# BANK_S_CAPACITORS.net
KiCad netlist of a schematic drawn in Altium Designer
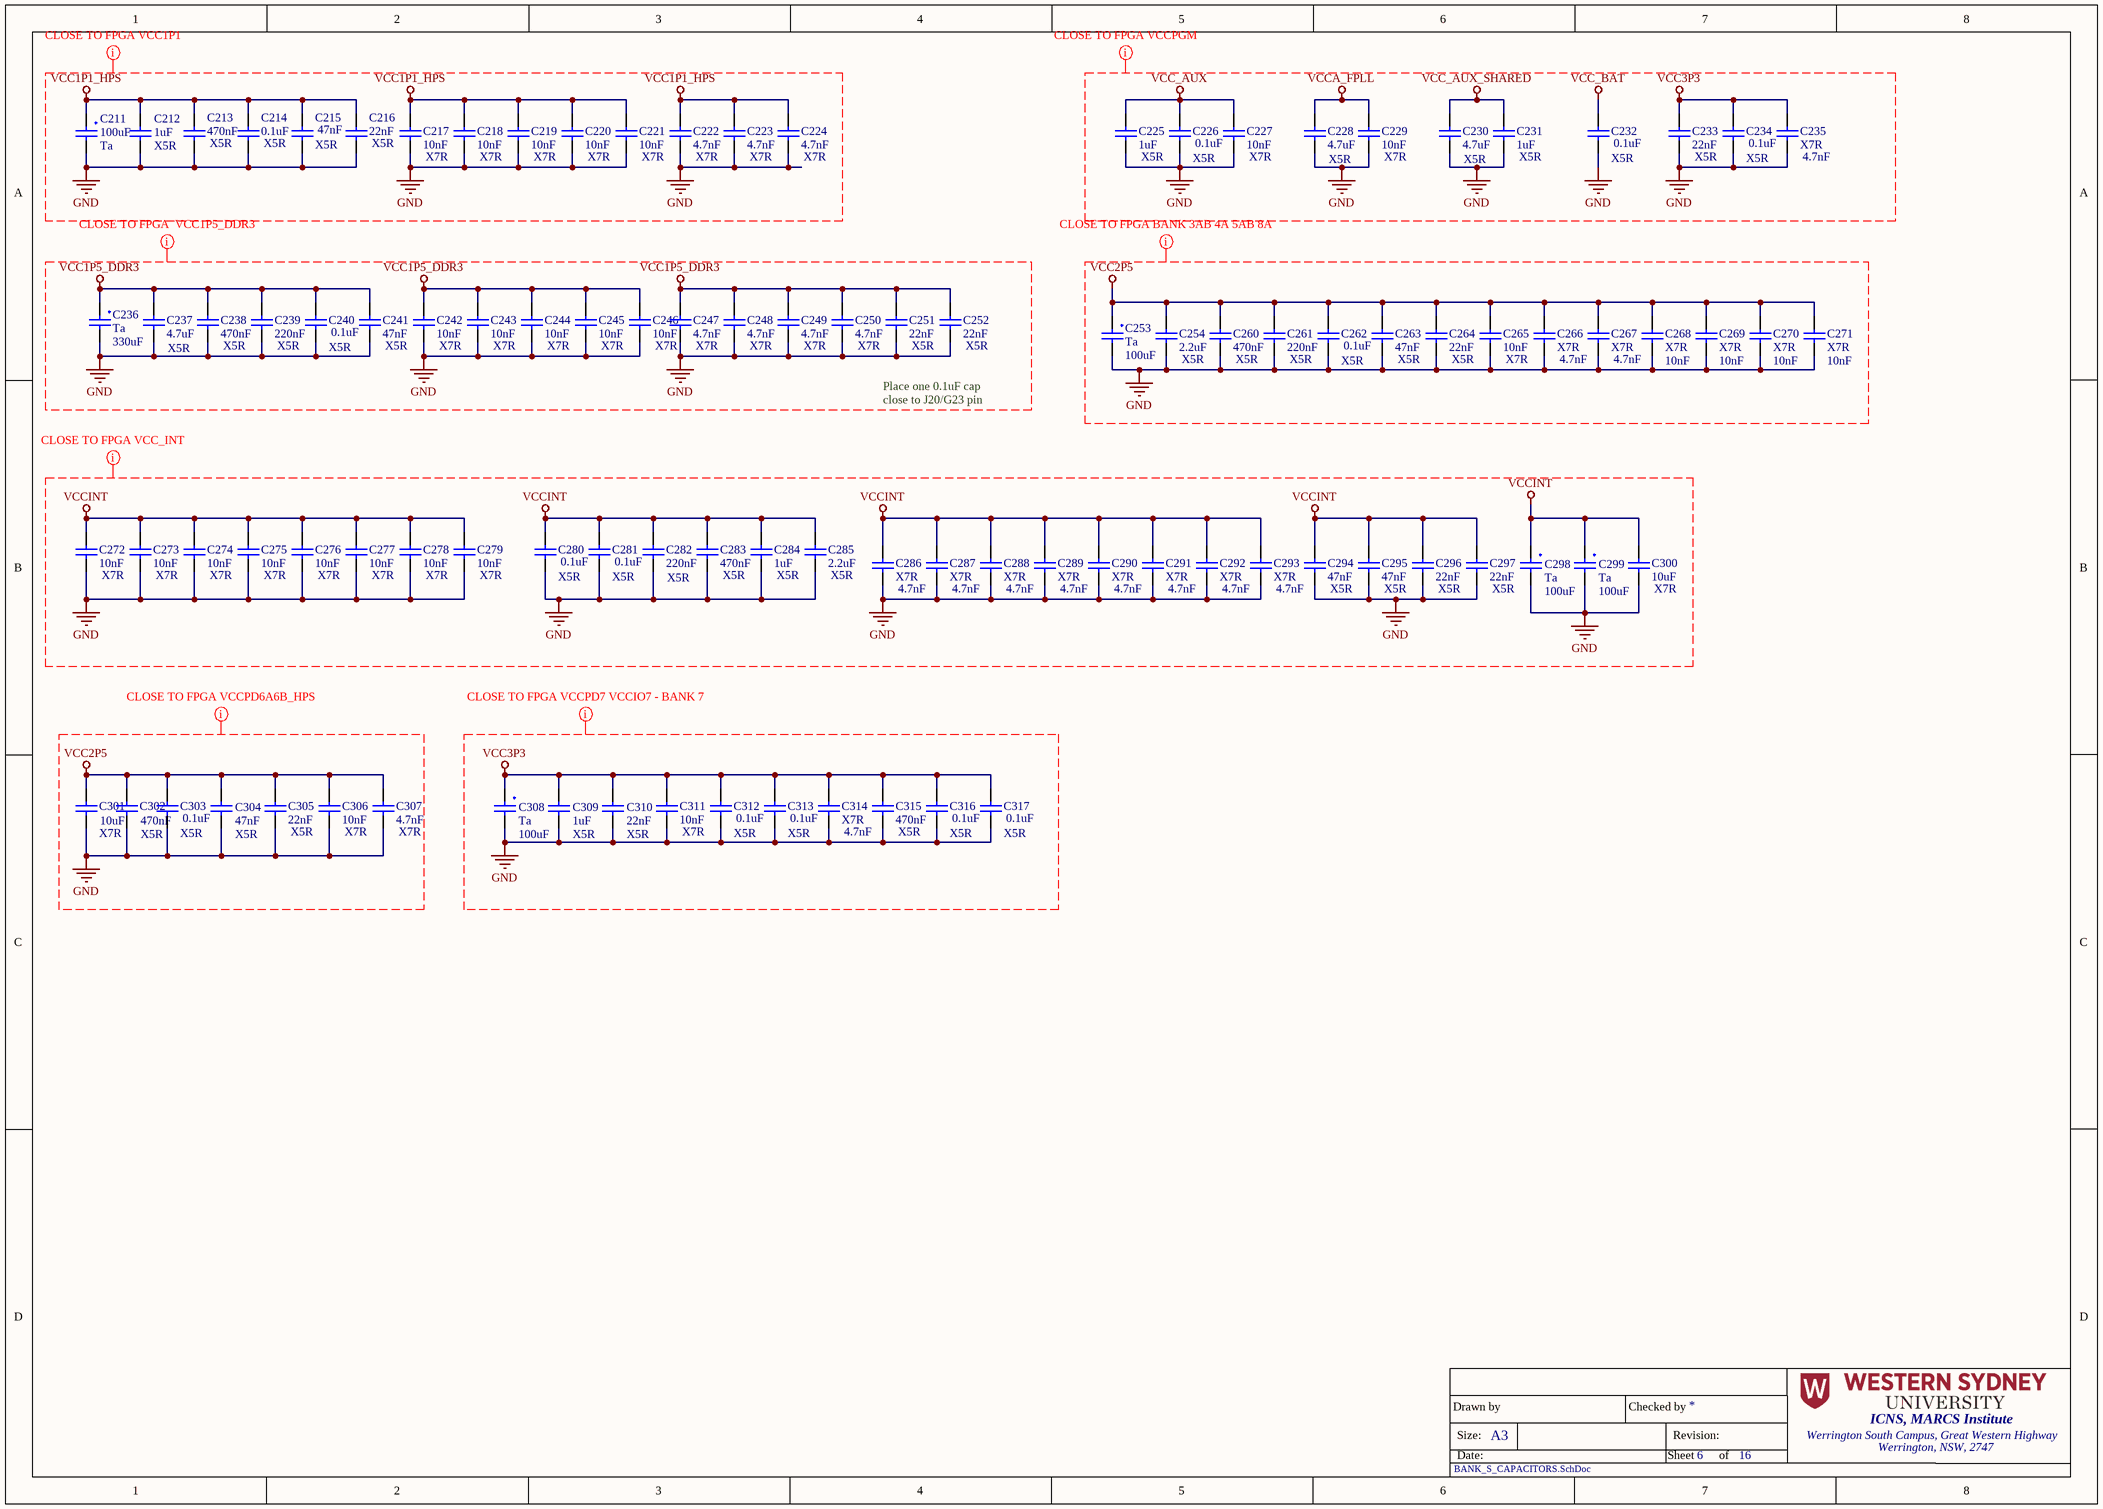
[diagram p0: BANK_S_CAPACITORS.SchDoc]

(export (version "E")
  (design (tool "Eeschema 10.0.6"))
  (components
    (comp (ref "C211")
      (value "100uF")
      (footprint "CAPCP 0805 (2012)")
      (description "Cap Tant Solid 100uF 6.3V R CASE 20% (2 X 1.35 X 1.35mm) SMD 2012-15 5 Ohm 125°C Plastic T/R")
      (fields
        (field (name "TOLERANCE") "20%")
        (field (name "DIELECTRIC") "Ta")
        (field (name "Comment") "TLCR107M006RTA")
      )
      (libsource (lib "") (part "Symbol_1"))
    )
    (comp (ref "C212")
      (value "1uF")
      (footprint "CAP 0201 (0603)")
      (description "Cap Ceramic 1uF 10V X5R 10% Pad SMD 0201 85C T/R")
      (fields
        (field (name "TOLERANCE") "10%")
        (field (name "DIELECTRIC") "X5R")
        (field (name "MANUFACTURER") "Samsung")
      )
      (libsource (lib "Western Sydney University - ICNS") (part "Symbol"))
    )
    (comp (ref "C213")
      (value "470nF")
      (footprint "CAP 0201 (0603)")
      (description "Cap Multilayer Ceramic 0.47 uF 10V X5R  0201 10% RoHS  (High dielectric type)")
      (fields
        (field (name "DIELECTRIC") "X5R")
        (field (name "MANUFACTURER") "Taiyo Yuden")
        (field (name "MANUFACTURER PART NUMBER") "LMK063BBJ474KPLF")
      )
      (libsource (lib "Western Sydney University - ICNS") (part "LMK063BBJ474KPLF"))
    )
    (comp (ref "C214")
      (value "0.1uF")
      (footprint "CAP 0201 (0603)")
      (description "Cap Ceramic 0.1uF 10V X5R 10% Pad SMD 0201 85C T/R")
      (fields
        (field (name "DIELECTRIC") "X5R")
        (field (name "MANUFACTURER") "Samsung")
        (field (name "MANUFACTURER PART NUMBER") "CL03A104KP3NNNC")
      )
      (libsource (lib "Western Sydney University - ICNS") (part "CL03A104KP3NNNC"))
    )
    (comp (ref "C215")
      (value "47nF")
      (footprint "CAP 0201 (0603)")
      (description "Cap Multilayer Ceramic 47nF 6.3V X5R SMT 0201±10% Tolerance")
      (fields
        (field (name "MANUFACTURER") "Murata")
        (field (name "TOLERANCE") "10%")
        (field (name "DIELECTRIC") "X5R")
      )
      (libsource (lib "Western Sydney University - ICNS") (part "Symbol"))
    )
    (comp (ref "C216")
      (value "22nF")
      (footprint "CAP 0201 (0603)")
      (description "Cap Multilayer Ceramic 22nF 10V X5R 0201 ±10% Tolerance")
      (fields
        (field (name "DIELECTRIC") "X5R")
        (field (name "TOLERANCE") "10%")
        (field (name "MANUFACTURER PART NUMBER") "CC0201KRX5R6BB223")
      )
      (libsource (lib "") (part "Symbol_2"))
    )
    (comp (ref "C217")
      (value "10nF")
      (footprint "CAP 0201 (0603)")
      (description "Cap Multilayer Ceramic 10nF 10V X7R 0201 ±10 % Tolerance SMT")
      (fields
        (field (name "VOLTAGE") "10V")
        (field (name "DIELECTRIC") "X7R")
        (field (name "TOLERANCE") "10%")
      )
      (libsource (lib "") (part "Symbol_2"))
    )
    (comp (ref "C218")
      (value "10nF")
      (footprint "CAP 0201 (0603)")
      (description "Cap Multilayer Ceramic 10nF 10V X7R 0201 ±10 % Tolerance SMT")
      (fields
        (field (name "VOLTAGE") "10V")
        (field (name "DIELECTRIC") "X7R")
        (field (name "TOLERANCE") "10%")
      )
      (libsource (lib "") (part "Symbol_2"))
    )
    (comp (ref "C219")
      (value "10nF")
      (footprint "CAP 0201 (0603)")
      (description "Cap Multilayer Ceramic 10nF 10V X7R 0201 ±10 % Tolerance SMT")
      (fields
        (field (name "VOLTAGE") "10V")
        (field (name "DIELECTRIC") "X7R")
        (field (name "TOLERANCE") "10%")
      )
      (libsource (lib "") (part "Symbol_2"))
    )
    (comp (ref "C220")
      (value "10nF")
      (footprint "CAP 0201 (0603)")
      (description "Cap Multilayer Ceramic 10nF 10V X7R 0201 ±10 % Tolerance SMT")
      (fields
        (field (name "VOLTAGE") "10V")
        (field (name "DIELECTRIC") "X7R")
        (field (name "TOLERANCE") "10%")
      )
      (libsource (lib "") (part "Symbol_2"))
    )
    (comp (ref "C221")
      (value "10nF")
      (footprint "CAP 0201 (0603)")
      (description "Cap Multilayer Ceramic 10nF 10V X7R 0201 ±10 % Tolerance SMT")
      (fields
        (field (name "VOLTAGE") "10V")
        (field (name "DIELECTRIC") "X7R")
        (field (name "TOLERANCE") "10%")
      )
      (libsource (lib "") (part "Symbol_2"))
    )
    (comp (ref "C222")
      (value "4.7nF")
      (footprint "CAP 0201 (0603)")
      (description "Cap Ceramic 4.7nF 6.3V X7R 10% Pad SMD 0201 125C Automotive T/R")
      (fields
        (field (name "DIELECTRIC") "X7R")
        (field (name "TOLERANCE") "10%")
        (field (name "MANUFACTURER PART NUMBER") "CC0201KRX7R5BB472")
      )
      (libsource (lib "Western Sydney University - ICNS") (part "Symbol"))
    )
    (comp (ref "C223")
      (value "4.7nF")
      (footprint "CAP 0201 (0603)")
      (description "Cap Ceramic 4.7nF 6.3V X7R 10% Pad SMD 0201 125C Automotive T/R")
      (fields
        (field (name "DIELECTRIC") "X7R")
        (field (name "TOLERANCE") "10%")
        (field (name "MANUFACTURER PART NUMBER") "CC0201KRX7R5BB472")
      )
      (libsource (lib "Western Sydney University - ICNS") (part "Symbol"))
    )
    (comp (ref "C224")
      (value "4.7nF")
      (footprint "CAP 0201 (0603)")
      (description "Cap Ceramic 4.7nF 6.3V X7R 10% Pad SMD 0201 125C Automotive T/R")
      (fields
        (field (name "DIELECTRIC") "X7R")
        (field (name "TOLERANCE") "10%")
        (field (name "MANUFACTURER PART NUMBER") "CC0201KRX7R5BB472")
      )
      (libsource (lib "Western Sydney University - ICNS") (part "Symbol"))
    )
    (comp (ref "C225")
      (value "1uF")
      (footprint "CAP 0201 (0603)")
      (description "Cap Ceramic 1uF 10V X5R 10% Pad SMD 0201 85C T/R")
      (fields
        (field (name "DIELECTRIC") "X5R")
        (field (name "TOLERANCE") "10%")
        (field (name "MANUFACTURER") "Samsung")
      )
      (libsource (lib "Western Sydney University - ICNS") (part "Symbol"))
    )
    (comp (ref "C226")
      (value "0.1uF")
      (footprint "CAP 0201 (0603)")
      (description "Cap Ceramic 0.1uF 10V X5R 10% Pad SMD 0201 85C T/R")
      (fields
        (field (name "MANUFACTURER") "Samsung")
        (field (name "TOLERANCE") "10%")
        (field (name "DIELECTRIC") "X5R")
      )
      (libsource (lib "Western Sydney University - ICNS") (part "CL03A104KP3NNNC"))
    )
    (comp (ref "C227")
      (value "10nF")
      (footprint "CAP 0201 (0603)")
      (description "Cap Multilayer Ceramic 10nF 10V X7R 0201 ±10 % Tolerance SMT")
      (fields
        (field (name "VOLTAGE") "10V")
        (field (name "DIELECTRIC") "X7R")
        (field (name "TOLERANCE") "10%")
      )
      (libsource (lib "") (part "Symbol_2"))
    )
    (comp (ref "C228")
      (value "4.7uF")
      (footprint "CAP 0402 (1005)")
      (description "Cap Multilayer Ceramic 4.7uF 10 V X5R ±10 % SMT 0402  C Series")
      (fields
        (field (name "TOLERANCE") "10%")
        (field (name "DIELECTRIC") "X5R")
        (field (name "MANUFACTURER") "TDK")
      )
      (libsource (lib "Western Sydney University - ICNS") (part "Symbol"))
    )
    (comp (ref "C229")
      (value "10nF")
      (footprint "CAP 0201 (0603)")
      (description "Cap Multilayer Ceramic 10nF 10V X7R 0201 ±10 % Tolerance SMT")
      (fields
        (field (name "VOLTAGE") "10V")
        (field (name "DIELECTRIC") "X7R")
        (field (name "TOLERANCE") "10%")
      )
      (libsource (lib "") (part "Symbol_2"))
    )
    (comp (ref "C230")
      (value "4.7uF")
      (footprint "CAP 0402 (1005)")
      (description "Cap Multilayer Ceramic 4.7uF 10 V X5R ±10 % SMT 0402  C Series")
      (fields
        (field (name "TOLERANCE") "10%")
        (field (name "DIELECTRIC") "X5R")
        (field (name "MANUFACTURER") "TDK")
      )
      (libsource (lib "Western Sydney University - ICNS") (part "Symbol"))
    )
    (comp (ref "C231")
      (value "1uF")
      (footprint "CAP 0201 (0603)")
      (description "Cap Ceramic 1uF 10V X5R 10% Pad SMD 0201 85C T/R")
      (fields
        (field (name "DIELECTRIC") "X5R")
        (field (name "TOLERANCE") "10%")
        (field (name "MANUFACTURER") "Samsung")
      )
      (libsource (lib "Western Sydney University - ICNS") (part "Symbol"))
    )
    (comp (ref "C232")
      (value "0.1uF")
      (footprint "CAP 0201 (0603)")
      (description "Cap Ceramic 0.1uF 10V X5R 10% Pad SMD 0201 85C T/R")
      (fields
        (field (name "MANUFACTURER") "Samsung")
        (field (name "TOLERANCE") "10%")
        (field (name "DIELECTRIC") "X5R")
      )
      (libsource (lib "Western Sydney University - ICNS") (part "CL03A104KP3NNNC"))
    )
    (comp (ref "C233")
      (value "22nF")
      (footprint "CAP 0201 (0603)")
      (description "Cap Multilayer Ceramic 22nF 10V X5R 0201 ±10% Tolerance")
      (fields
        (field (name "DIELECTRIC") "X5R")
        (field (name "TOLERANCE") "10%")
        (field (name "MANUFACTURER PART NUMBER") "CC0201KRX5R6BB223")
      )
      (libsource (lib "") (part "Symbol_2"))
    )
    (comp (ref "C234")
      (value "0.1uF")
      (footprint "CAP 0201 (0603)")
      (description "Cap Ceramic 0.1uF 10V X5R 10% Pad SMD 0201 85C T/R")
      (fields
        (field (name "MANUFACTURER") "Samsung")
        (field (name "TOLERANCE") "10%")
        (field (name "DIELECTRIC") "X5R")
      )
      (libsource (lib "Western Sydney University - ICNS") (part "CL03A104KP3NNNC"))
    )
    (comp (ref "C235")
      (value "CC0201KRX7R5BB472")
      (footprint "CAP 0201 (0603)")
      (description "Cap Ceramic 4.7nF 6.3V X7R 10% Pad SMD 0201 125C Automotive T/R")
      (fields
        (field (name "TOLERANCE") "10%")
        (field (name "MANUFACTURER") "Yageo")
        (field (name "CAPACITANCE") "4.7nF")
        (field (name "DIELECTRIC") "X7R")
      )
      (libsource (lib "Western Sydney University - ICNS") (part "Symbol"))
    )
    (comp (ref "C236")
      (value "330uF")
      (footprint "CAPMP7343X31N")
      (description "Cap Tant Solid 330uF 6.3V D CASE 10% (7.3 X 4.3 X 2.8mm) SMD 7343-31 0.1 Ohm 125 C T/R")
      (fields
        (field (name "VOLTAGE") "6.3V")
        (field (name "TOLERANCE") "20%")
        (field (name "DIELECTRIC") "Ta")
      )
      (libsource (lib "") (part "Symbol_1"))
    )
    (comp (ref "C237")
      (value "4.7uF")
      (footprint "CAP 0402 (1005)")
      (description "Cap Multilayer Ceramic 4.7uF 10 V X5R ±10 % SMT 0402  C Series")
      (fields
        (field (name "TOLERANCE") "10%")
        (field (name "DIELECTRIC") "X5R")
        (field (name "MANUFACTURER") "TDK")
      )
      (libsource (lib "Western Sydney University - ICNS") (part "Symbol"))
    )
    (comp (ref "C238")
      (value "470nF")
      (footprint "CAP 0201 (0603)")
      (description "Cap Multilayer Ceramic 0.47 uF 10V X5R  0201 10% RoHS  (High dielectric type)")
      (fields
        (field (name "DIELECTRIC") "X5R")
        (field (name "MANUFACTURER") "Taiyo Yuden")
        (field (name "MANUFACTURER PART NUMBER") "LMK063BBJ474KPLF")
      )
      (libsource (lib "Western Sydney University - ICNS") (part "LMK063BBJ474KPLF"))
    )
    (comp (ref "C239")
      (value "220nF")
      (footprint "CAP 0201 (0603)")
      (description "Cap Multilayer Ceramic 220nF 10V X5R 0201 ±10% Tolerance")
      (fields
        (field (name "DIELECTRIC") "X5R")
        (field (name "MANUFACTURER") "Murata")
        (field (name "MANUFACTURER PART NUMBER") "GRM033R61A224KE90D")
      )
      (libsource (lib "Western Sydney University - ICNS") (part "Symbol"))
    )
    (comp (ref "C240")
      (value "0.1uF")
      (footprint "CAP 0201 (0603)")
      (description "Cap Ceramic 0.1uF 10V X5R 10% Pad SMD 0201 85C T/R")
      (fields
        (field (name "MANUFACTURER") "Samsung")
        (field (name "TOLERANCE") "10%")
        (field (name "DIELECTRIC") "X5R")
      )
      (libsource (lib "Western Sydney University - ICNS") (part "CL03A104KP3NNNC"))
    )
    (comp (ref "C241")
      (value "47nF")
      (footprint "CAP 0201 (0603)")
      (description "Cap Multilayer Ceramic 47nF 6.3V X5R SMT 0201±10% Tolerance")
      (fields
        (field (name "DIELECTRIC") "X5R")
        (field (name "TOLERANCE") "10%")
        (field (name "MANUFACTURER PART NUMBER") "GRM033R60J473KE19D")
      )
      (libsource (lib "Western Sydney University - ICNS") (part "Symbol"))
    )
    (comp (ref "C242")
      (value "10nF")
      (footprint "CAP 0201 (0603)")
      (description "Cap Multilayer Ceramic 10nF 10V X7R 0201 ±10 % Tolerance SMT")
      (fields
        (field (name "VOLTAGE") "10V")
        (field (name "DIELECTRIC") "X7R")
        (field (name "TOLERANCE") "10%")
      )
      (libsource (lib "") (part "Symbol_2"))
    )
    (comp (ref "C243")
      (value "10nF")
      (footprint "CAP 0201 (0603)")
      (description "Cap Multilayer Ceramic 10nF 10V X7R 0201 ±10 % Tolerance SMT")
      (fields
        (field (name "VOLTAGE") "10V")
        (field (name "DIELECTRIC") "X7R")
        (field (name "TOLERANCE") "10%")
      )
      (libsource (lib "") (part "Symbol_2"))
    )
    (comp (ref "C244")
      (value "10nF")
      (footprint "CAP 0201 (0603)")
      (description "Cap Multilayer Ceramic 10nF 10V X7R 0201 ±10 % Tolerance SMT")
      (fields
        (field (name "VOLTAGE") "10V")
        (field (name "DIELECTRIC") "X7R")
        (field (name "TOLERANCE") "10%")
      )
      (libsource (lib "") (part "Symbol_2"))
    )
    (comp (ref "C245")
      (value "10nF")
      (footprint "CAP 0201 (0603)")
      (description "Cap Multilayer Ceramic 10nF 10V X7R 0201 ±10 % Tolerance SMT")
      (fields
        (field (name "VOLTAGE") "10V")
        (field (name "DIELECTRIC") "X7R")
        (field (name "TOLERANCE") "10%")
      )
      (libsource (lib "") (part "Symbol_2"))
    )
    (comp (ref "C246")
      (value "10nF")
      (footprint "CAP 0201 (0603)")
      (description "Cap Multilayer Ceramic 10nF 10V X7R 0201 ±10 % Tolerance SMT")
      (fields
        (field (name "VOLTAGE") "10V")
        (field (name "DIELECTRIC") "X7R")
        (field (name "TOLERANCE") "10%")
      )
      (libsource (lib "") (part "Symbol_2"))
    )
    (comp (ref "C247")
      (value "4.7nF")
      (footprint "CAP 0201 (0603)")
      (description "Cap Ceramic 4.7nF 6.3V X7R 10% Pad SMD 0201 125C Automotive T/R")
      (fields
        (field (name "DIELECTRIC") "X7R")
        (field (name "TOLERANCE") "10%")
        (field (name "MANUFACTURER PART NUMBER") "CC0201KRX7R5BB472")
      )
      (libsource (lib "Western Sydney University - ICNS") (part "Symbol"))
    )
    (comp (ref "C248")
      (value "4.7nF")
      (footprint "CAP 0201 (0603)")
      (description "Cap Ceramic 4.7nF 6.3V X7R 10% Pad SMD 0201 125C Automotive T/R")
      (fields
        (field (name "DIELECTRIC") "X7R")
        (field (name "TOLERANCE") "10%")
        (field (name "MANUFACTURER PART NUMBER") "CC0201KRX7R5BB472")
      )
      (libsource (lib "Western Sydney University - ICNS") (part "Symbol"))
    )
    (comp (ref "C249")
      (value "4.7nF")
      (footprint "CAP 0201 (0603)")
      (description "Cap Ceramic 4.7nF 6.3V X7R 10% Pad SMD 0201 125C Automotive T/R")
      (fields
        (field (name "DIELECTRIC") "X7R")
        (field (name "TOLERANCE") "10%")
        (field (name "MANUFACTURER PART NUMBER") "CC0201KRX7R5BB472")
      )
      (libsource (lib "Western Sydney University - ICNS") (part "Symbol"))
    )
    (comp (ref "C250")
      (value "4.7nF")
      (footprint "CAP 0201 (0603)")
      (description "Cap Ceramic 4.7nF 6.3V X7R 10% Pad SMD 0201 125C Automotive T/R")
      (fields
        (field (name "DIELECTRIC") "X7R")
        (field (name "TOLERANCE") "10%")
        (field (name "MANUFACTURER PART NUMBER") "CC0201KRX7R5BB472")
      )
      (libsource (lib "Western Sydney University - ICNS") (part "Symbol"))
    )
    (comp (ref "C251")
      (value "22nF")
      (footprint "CAP 0201 (0603)")
      (description "Cap Multilayer Ceramic 22nF 10V X5R 0201 ±10% Tolerance")
      (fields
        (field (name "DIELECTRIC") "X5R")
        (field (name "TOLERANCE") "10%")
        (field (name "MANUFACTURER PART NUMBER") "CC0201KRX5R6BB223")
      )
      (libsource (lib "") (part "Symbol_2"))
    )
    (comp (ref "C252")
      (value "22nF")
      (footprint "CAP 0201 (0603)")
      (description "Cap Multilayer Ceramic 22nF 10V X5R 0201 ±10% Tolerance")
      (fields
        (field (name "DIELECTRIC") "X5R")
        (field (name "TOLERANCE") "10%")
        (field (name "MANUFACTURER PART NUMBER") "CC0201KRX5R6BB223")
      )
      (libsource (lib "") (part "Symbol_2"))
    )
    (comp (ref "C253")
      (value "100uF")
      (footprint "CAPCP 0805 (2012)")
      (description "Cap Tant Solid 100uF 6.3V R CASE 20% (2 X 1.35 X 1.35mm) SMD 2012-15 5 Ohm 125°C Plastic T/R")
      (fields
        (field (name "TOLERANCE") "20%")
        (field (name "DIELECTRIC") "Ta")
        (field (name "Comment") "TLCR107M006RTA")
      )
      (libsource (lib "") (part "Symbol_1"))
    )
    (comp (ref "C254")
      (value "2.2uF")
      (footprint "CAP 0201 (0603)")
      (description "Cap Ceramic 2.2uF 10VDC X5R 10% SMD 0201 Paper T/R  Monolithic")
      (fields
        (field (name "DIELECTRIC") "X5R")
        (field (name "MANUFACTURER") "Murata")
        (field (name "MANUFACTURER PART NUMBER") "GRM033R61A225KE47J")
      )
      (libsource (lib "Western Sydney University - ICNS") (part "Symbol"))
    )
    (comp (ref "C260")
      (value "470nF")
      (footprint "CAP 0201 (0603)")
      (description "Cap Multilayer Ceramic 0.47 uF 10V X5R  0201 10% RoHS  (High dielectric type)")
      (fields
        (field (name "DIELECTRIC") "X5R")
        (field (name "MANUFACTURER") "Taiyo Yuden")
        (field (name "MANUFACTURER PART NUMBER") "LMK063BBJ474KPLF")
      )
      (libsource (lib "Western Sydney University - ICNS") (part "LMK063BBJ474KPLF"))
    )
    (comp (ref "C261")
      (value "220nF")
      (footprint "CAP 0201 (0603)")
      (description "Cap Multilayer Ceramic 220nF 10V X5R 0201 ±10% Tolerance")
      (fields
        (field (name "DIELECTRIC") "X5R")
        (field (name "TOLERANCE") "10%")
        (field (name "MANUFACTURER PART NUMBER") "GRM033R61A224KE90D")
      )
      (libsource (lib "Western Sydney University - ICNS") (part "Symbol"))
    )
    (comp (ref "C262")
      (value "0.1uF")
      (footprint "CAP 0201 (0603)")
      (description "Cap Ceramic 0.1uF 10V X5R 10% Pad SMD 0201 85C T/R")
      (fields
        (field (name "MANUFACTURER") "Samsung")
        (field (name "TOLERANCE") "10%")
        (field (name "DIELECTRIC") "X5R")
      )
      (libsource (lib "Western Sydney University - ICNS") (part "CL03A104KP3NNNC"))
    )
    (comp (ref "C263")
      (value "47nF")
      (footprint "CAP 0201 (0603)")
      (description "Cap Multilayer Ceramic 47nF 6.3V X5R SMT 0201±10% Tolerance")
      (fields
        (field (name "TOLERANCE") "10%")
        (field (name "DIELECTRIC") "X5R")
        (field (name "MANUFACTURER") "Murata")
      )
      (libsource (lib "Western Sydney University - ICNS") (part "Symbol"))
    )
    (comp (ref "C264")
      (value "22nF")
      (footprint "CAP 0201 (0603)")
      (description "Cap Multilayer Ceramic 22nF 10V X5R 0201 ±10% Tolerance")
      (fields
        (field (name "DIELECTRIC") "X5R")
        (field (name "TOLERANCE") "10%")
        (field (name "MANUFACTURER PART NUMBER") "CC0201KRX5R6BB223")
      )
      (libsource (lib "") (part "Symbol_2"))
    )
    (comp (ref "C265")
      (value "10nF")
      (footprint "CAP 0201 (0603)")
      (description "Cap Multilayer Ceramic 10nF 10V X7R 0201 ±10 % Tolerance SMT")
      (fields
        (field (name "VOLTAGE") "10V")
        (field (name "DIELECTRIC") "X7R")
        (field (name "TOLERANCE") "10%")
      )
      (libsource (lib "") (part "Symbol_2"))
    )
    (comp (ref "C266")
      (value "CC0201KRX7R5BB472")
      (footprint "CAP 0201 (0603)")
      (description "Cap Ceramic 4.7nF 6.3V X7R 10% Pad SMD 0201 125C Automotive T/R")
      (fields
        (field (name "TOLERANCE") "10%")
        (field (name "MANUFACTURER") "Yageo")
        (field (name "CAPACITANCE") "4.7nF")
        (field (name "DIELECTRIC") "X7R")
      )
      (libsource (lib "Western Sydney University - ICNS") (part "Symbol"))
    )
    (comp (ref "C267")
      (value "CC0201KRX7R5BB472")
      (footprint "CAP 0201 (0603)")
      (description "Cap Ceramic 4.7nF 6.3V X7R 10% Pad SMD 0201 125C Automotive T/R")
      (fields
        (field (name "TOLERANCE") "10%")
        (field (name "MANUFACTURER") "Yageo")
        (field (name "CAPACITANCE") "4.7nF")
        (field (name "DIELECTRIC") "X7R")
      )
      (libsource (lib "Western Sydney University - ICNS") (part "Symbol"))
    )
    (comp (ref "C268")
      (value "10nF")
      (footprint "CAP 0201 (0603)")
      (description "Cap Multilayer Ceramic 10nF 10V X7R 0201 ±10 % Tolerance SMT")
      (fields
        (field (name "VOLTAGE") "10V")
        (field (name "DIELECTRIC") "X7R")
        (field (name "TOLERANCE") "10%")
      )
      (libsource (lib "") (part "Symbol_2"))
    )
    (comp (ref "C269")
      (value "10nF")
      (footprint "CAP 0201 (0603)")
      (description "Cap Multilayer Ceramic 10nF 10V X7R 0201 ±10 % Tolerance SMT")
      (fields
        (field (name "VOLTAGE") "10V")
        (field (name "DIELECTRIC") "X7R")
        (field (name "TOLERANCE") "10%")
      )
      (libsource (lib "") (part "Symbol_2"))
    )
    (comp (ref "C270")
      (value "10nF")
      (footprint "CAP 0201 (0603)")
      (description "Cap Multilayer Ceramic 10nF 10V X7R 0201 ±10 % Tolerance SMT")
      (fields
        (field (name "VOLTAGE") "10V")
        (field (name "DIELECTRIC") "X7R")
        (field (name "TOLERANCE") "10%")
      )
      (libsource (lib "") (part "Symbol_2"))
    )
    (comp (ref "C271")
      (value "10nF")
      (footprint "CAP 0201 (0603)")
      (description "Cap Multilayer Ceramic 10nF 10V X7R 0201 ±10 % Tolerance SMT")
      (fields
        (field (name "VOLTAGE") "10V")
        (field (name "DIELECTRIC") "X7R")
        (field (name "TOLERANCE") "10%")
      )
      (libsource (lib "") (part "Symbol_2"))
    )
    (comp (ref "C272")
      (value "10nF")
      (footprint "CAP 0201 (0603)")
      (description "Cap Multilayer Ceramic 10nF 10V X7R 0201 ±10 % Tolerance SMT")
      (fields
        (field (name "VOLTAGE") "10V")
        (field (name "DIELECTRIC") "X7R")
        (field (name "TOLERANCE") "10%")
      )
      (libsource (lib "") (part "Symbol_2"))
    )
    (comp (ref "C273")
      (value "10nF")
      (footprint "CAP 0201 (0603)")
      (description "Cap Multilayer Ceramic 10nF 10V X7R 0201 ±10 % Tolerance SMT")
      (fields
        (field (name "VOLTAGE") "10V")
        (field (name "DIELECTRIC") "X7R")
        (field (name "TOLERANCE") "10%")
      )
      (libsource (lib "") (part "Symbol_2"))
    )
    (comp (ref "C274")
      (value "10nF")
      (footprint "CAP 0201 (0603)")
      (description "Cap Multilayer Ceramic 10nF 10V X7R 0201 ±10 % Tolerance SMT")
      (fields
        (field (name "VOLTAGE") "10V")
        (field (name "DIELECTRIC") "X7R")
        (field (name "TOLERANCE") "10%")
      )
      (libsource (lib "") (part "Symbol_2"))
    )
    (comp (ref "C275")
      (value "10nF")
      (footprint "CAP 0201 (0603)")
      (description "Cap Multilayer Ceramic 10nF 10V X7R 0201 ±10 % Tolerance SMT")
      (fields
        (field (name "VOLTAGE") "10V")
        (field (name "DIELECTRIC") "X7R")
        (field (name "TOLERANCE") "10%")
      )
      (libsource (lib "") (part "Symbol_2"))
    )
    (comp (ref "C276")
      (value "10nF")
      (footprint "CAP 0201 (0603)")
      (description "Cap Multilayer Ceramic 10nF 10V X7R 0201 ±10 % Tolerance SMT")
      (fields
        (field (name "VOLTAGE") "10V")
        (field (name "DIELECTRIC") "X7R")
        (field (name "TOLERANCE") "10%")
      )
      (libsource (lib "") (part "Symbol_2"))
    )
    (comp (ref "C277")
      (value "10nF")
      (footprint "CAP 0201 (0603)")
      (description "Cap Multilayer Ceramic 10nF 10V X7R 0201 ±10 % Tolerance SMT")
      (fields
        (field (name "VOLTAGE") "10V")
        (field (name "DIELECTRIC") "X7R")
        (field (name "TOLERANCE") "10%")
      )
      (libsource (lib "") (part "Symbol_2"))
    )
    (comp (ref "C278")
      (value "10nF")
      (footprint "CAP 0201 (0603)")
      (description "Cap Multilayer Ceramic 10nF 10V X7R 0201 ±10 % Tolerance SMT")
      (fields
        (field (name "VOLTAGE") "10V")
        (field (name "DIELECTRIC") "X7R")
        (field (name "TOLERANCE") "10%")
      )
      (libsource (lib "") (part "Symbol_2"))
    )
    (comp (ref "C279")
      (value "10nF")
      (footprint "CAP 0201 (0603)")
      (description "Cap Multilayer Ceramic 10nF 10V X7R 0201 ±10 % Tolerance SMT")
      (fields
        (field (name "VOLTAGE") "10V")
        (field (name "DIELECTRIC") "X7R")
        (field (name "TOLERANCE") "10%")
      )
      (libsource (lib "") (part "Symbol_2"))
    )
    (comp (ref "C280")
      (value "0.1uF")
      (footprint "CAP 0201 (0603)")
      (description "Cap Ceramic 0.1uF 10V X5R 10% Pad SMD 0201 85C T/R")
      (fields
        (field (name "MANUFACTURER") "Samsung")
        (field (name "TOLERANCE") "10%")
        (field (name "DIELECTRIC") "X5R")
      )
      (libsource (lib "Western Sydney University - ICNS") (part "CL03A104KP3NNNC"))
    )
    (comp (ref "C281")
      (value "0.1uF")
      (footprint "CAP 0201 (0603)")
      (description "Cap Ceramic 0.1uF 10V X5R 10% Pad SMD 0201 85C T/R")
      (fields
        (field (name "MANUFACTURER") "Samsung")
        (field (name "TOLERANCE") "10%")
        (field (name "DIELECTRIC") "X5R")
      )
      (libsource (lib "Western Sydney University - ICNS") (part "CL03A104KP3NNNC"))
    )
    (comp (ref "C282")
      (value "220nF")
      (footprint "CAP 0201 (0603)")
      (description "Cap Multilayer Ceramic 220nF 10V X5R 0201 ±10% Tolerance")
      (fields
        (field (name "DIELECTRIC") "X5R")
        (field (name "TOLERANCE") "10%")
        (field (name "MANUFACTURER PART NUMBER") "GRM033R61A224KE90D")
      )
      (libsource (lib "Western Sydney University - ICNS") (part "Symbol"))
    )
    (comp (ref "C283")
      (value "470nF")
      (footprint "CAP 0201 (0603)")
      (description "Cap Multilayer Ceramic 0.47 uF 10V X5R  0201 10% RoHS  (High dielectric type)")
      (fields
        (field (name "DIELECTRIC") "X5R")
        (field (name "MANUFACTURER") "Taiyo Yuden")
        (field (name "MANUFACTURER PART NUMBER") "LMK063BBJ474KPLF")
      )
      (libsource (lib "Western Sydney University - ICNS") (part "LMK063BBJ474KPLF"))
    )
    (comp (ref "C284")
      (value "1uF")
      (footprint "CAP 0201 (0603)")
      (description "Cap Ceramic 1uF 10V X5R 10% Pad SMD 0201 85C T/R")
      (fields
        (field (name "DIELECTRIC") "X5R")
        (field (name "TOLERANCE") "10%")
        (field (name "MANUFACTURER") "Samsung")
      )
      (libsource (lib "Western Sydney University - ICNS") (part "Symbol"))
    )
    (comp (ref "C285")
      (value "2.2uF")
      (footprint "CAP 0201 (0603)")
      (description "Cap Ceramic 2.2uF 10VDC X5R 10% SMD 0201 Paper T/R  Monolithic")
      (fields
        (field (name "DIELECTRIC") "X5R")
        (field (name "MANUFACTURER") "Murata")
        (field (name "MANUFACTURER PART NUMBER") "GRM033R61A225KE47J")
      )
      (libsource (lib "Western Sydney University - ICNS") (part "Symbol"))
    )
    (comp (ref "C286")
      (value "CC0201KRX7R5BB472")
      (footprint "CAP 0201 (0603)")
      (description "Cap Ceramic 4.7nF 6.3V X7R 10% Pad SMD 0201 125C Automotive T/R")
      (fields
        (field (name "TOLERANCE") "10%")
        (field (name "MANUFACTURER") "Yageo")
        (field (name "CAPACITANCE") "4.7nF")
        (field (name "DIELECTRIC") "X7R")
      )
      (libsource (lib "Western Sydney University - ICNS") (part "Symbol"))
    )
    (comp (ref "C287")
      (value "CC0201KRX7R5BB472")
      (footprint "CAP 0201 (0603)")
      (description "Cap Ceramic 4.7nF 6.3V X7R 10% Pad SMD 0201 125C Automotive T/R")
      (fields
        (field (name "TOLERANCE") "10%")
        (field (name "MANUFACTURER") "Yageo")
        (field (name "CAPACITANCE") "4.7nF")
        (field (name "DIELECTRIC") "X7R")
      )
      (libsource (lib "Western Sydney University - ICNS") (part "Symbol"))
    )
    (comp (ref "C288")
      (value "CC0201KRX7R5BB472")
      (footprint "CAP 0201 (0603)")
      (description "Cap Ceramic 4.7nF 6.3V X7R 10% Pad SMD 0201 125C Automotive T/R")
      (fields
        (field (name "TOLERANCE") "10%")
        (field (name "MANUFACTURER") "Yageo")
        (field (name "CAPACITANCE") "4.7nF")
        (field (name "DIELECTRIC") "X7R")
      )
      (libsource (lib "Western Sydney University - ICNS") (part "Symbol"))
    )
    (comp (ref "C289")
      (value "CC0201KRX7R5BB472")
      (footprint "CAP 0201 (0603)")
      (description "Cap Ceramic 4.7nF 6.3V X7R 10% Pad SMD 0201 125C Automotive T/R")
      (fields
        (field (name "TOLERANCE") "10%")
        (field (name "MANUFACTURER") "Yageo")
        (field (name "CAPACITANCE") "4.7nF")
        (field (name "DIELECTRIC") "X7R")
      )
      (libsource (lib "Western Sydney University - ICNS") (part "Symbol"))
    )
    (comp (ref "C290")
      (value "CC0201KRX7R5BB472")
      (footprint "CAP 0201 (0603)")
      (description "Cap Ceramic 4.7nF 6.3V X7R 10% Pad SMD 0201 125C Automotive T/R")
      (fields
        (field (name "TOLERANCE") "10%")
        (field (name "MANUFACTURER") "Yageo")
        (field (name "CAPACITANCE") "4.7nF")
        (field (name "DIELECTRIC") "X7R")
      )
      (libsource (lib "Western Sydney University - ICNS") (part "Symbol"))
    )
    (comp (ref "C291")
      (value "CC0201KRX7R5BB472")
      (footprint "CAP 0201 (0603)")
      (description "Cap Ceramic 4.7nF 6.3V X7R 10% Pad SMD 0201 125C Automotive T/R")
      (fields
        (field (name "TOLERANCE") "10%")
        (field (name "MANUFACTURER") "Yageo")
        (field (name "CAPACITANCE") "4.7nF")
        (field (name "DIELECTRIC") "X7R")
      )
      (libsource (lib "Western Sydney University - ICNS") (part "Symbol"))
    )
    (comp (ref "C292")
      (value "CC0201KRX7R5BB472")
      (footprint "CAP 0201 (0603)")
      (description "Cap Ceramic 4.7nF 6.3V X7R 10% Pad SMD 0201 125C Automotive T/R")
      (fields
        (field (name "TOLERANCE") "10%")
        (field (name "MANUFACTURER") "Yageo")
        (field (name "CAPACITANCE") "4.7nF")
        (field (name "DIELECTRIC") "X7R")
      )
      (libsource (lib "Western Sydney University - ICNS") (part "Symbol"))
    )
    (comp (ref "C293")
      (value "CC0201KRX7R5BB472")
      (footprint "CAP 0201 (0603)")
      (description "Cap Ceramic 4.7nF 6.3V X7R 10% Pad SMD 0201 125C Automotive T/R")
      (fields
        (field (name "TOLERANCE") "10%")
        (field (name "MANUFACTURER") "Yageo")
        (field (name "CAPACITANCE") "4.7nF")
        (field (name "DIELECTRIC") "X7R")
      )
      (libsource (lib "Western Sydney University - ICNS") (part "Symbol"))
    )
    (comp (ref "C294")
      (value "47nF")
      (footprint "CAP 0201 (0603)")
      (description "Cap Multilayer Ceramic 47nF 6.3V X5R SMT 0201±10% Tolerance")
      (fields
        (field (name "TOLERANCE") "10%")
        (field (name "DIELECTRIC") "X5R")
        (field (name "MANUFACTURER") "Murata")
      )
      (libsource (lib "Western Sydney University - ICNS") (part "Symbol"))
    )
    (comp (ref "C295")
      (value "47nF")
      (footprint "CAP 0201 (0603)")
      (description "Cap Multilayer Ceramic 47nF 6.3V X5R SMT 0201±10% Tolerance")
      (fields
        (field (name "TOLERANCE") "10%")
        (field (name "DIELECTRIC") "X5R")
        (field (name "MANUFACTURER") "Murata")
      )
      (libsource (lib "Western Sydney University - ICNS") (part "Symbol"))
    )
    (comp (ref "C296")
      (value "22nF")
      (footprint "CAP 0201 (0603)")
      (description "Cap Multilayer Ceramic 22nF 10V X5R 0201 ±10% Tolerance")
      (fields
        (field (name "DIELECTRIC") "X5R")
        (field (name "TOLERANCE") "10%")
        (field (name "MANUFACTURER PART NUMBER") "CC0201KRX5R6BB223")
      )
      (libsource (lib "") (part "Symbol_2"))
    )
    (comp (ref "C297")
      (value "22nF")
      (footprint "CAP 0201 (0603)")
      (description "Cap Multilayer Ceramic 22nF 10V X5R 0201 ±10% Tolerance")
      (fields
        (field (name "DIELECTRIC") "X5R")
        (field (name "TOLERANCE") "10%")
        (field (name "MANUFACTURER PART NUMBER") "CC0201KRX5R6BB223")
      )
      (libsource (lib "") (part "Symbol_2"))
    )
    (comp (ref "C298")
      (value "100uF")
      (footprint "CAPCP 0805 (2012)")
      (description "Cap Tant Solid 100uF 6.3V R CASE 20% (2 X 1.35 X 1.35mm) SMD 2012-15 5 Ohm 125°C Plastic T/R")
      (fields
        (field (name "TOLERANCE") "20%")
        (field (name "DIELECTRIC") "Ta")
        (field (name "Comment") "TLCR107M006RTA")
      )
      (libsource (lib "") (part "Symbol_1"))
    )
    (comp (ref "C299")
      (value "100uF")
      (footprint "CAPCP 0805 (2012)")
      (description "Cap Tant Solid 100uF 6.3V R CASE 20% (2 X 1.35 X 1.35mm) SMD 2012-15 5 Ohm 125°C Plastic T/R")
      (fields
        (field (name "TOLERANCE") "20%")
        (field (name "DIELECTRIC") "Ta")
        (field (name "Comment") "TLCR107M006RTA")
      )
      (libsource (lib "") (part "Symbol_1"))
    )
    (comp (ref "C300")
      (value "10uF")
      (footprint "CAP 0805 (2012)")
      (description "0805 10 uF 10 V ±10 % Tolerance X7R Surface Mount Multilayer Ceramic Capacitor")
      (fields
        (field (name "TOLERANCE") "10%")
        (field (name "DIELECTRIC") "X7R")
        (field (name "MANUFACTURER PART NUMBER") "GCM21BR71A106KE22K")
      )
      (libsource (lib "Western Sydney University - ICNS") (part "GCM21BR71A106KE22K"))
    )
    (comp (ref "C301")
      (value "GCM21BR71A106KE22K")
      (footprint "CAP 0805 (2012)")
      (description "0805 10 uF 10 V ±10 % Tolerance X7R Surface Mount Multilayer Ceramic Capacitor")
      (fields
        (field (name "DIELECTRIC") "X7R")
        (field (name "CAPACITANCE") "10uF")
        (field (name "MANUFACTURER") "Murata")
        (field (name "TOLERANCE") "10%")
      )
      (libsource (lib "Western Sydney University - ICNS") (part "GCM21BR71A106KE22K"))
    )
    (comp (ref "C302")
      (value "LMK063BBJ474KPLF")
      (footprint "CAP 0201 (0603)")
      (description "Cap Multilayer Ceramic 0.47 uF 10V X5R  0201 10% RoHS  (High dielectric type)")
      (fields
        (field (name "DIELECTRIC") "X5R")
        (field (name "CAPACITANCE") "470nF")
        (field (name "MANUFACTURER") "Taiyo Yuden")
      )
      (libsource (lib "Western Sydney University - ICNS") (part "LMK063BBJ474KPLF"))
    )
    (comp (ref "C303")
      (value "0.1uF")
      (footprint "CAP 0201 (0603)")
      (description "Cap Ceramic 0.1uF 10V X5R 10% Pad SMD 0201 85C T/R")
      (fields
        (field (name "MANUFACTURER") "Samsung")
        (field (name "TOLERANCE") "10%")
        (field (name "DIELECTRIC") "X5R")
      )
      (libsource (lib "Western Sydney University - ICNS") (part "CL03A104KP3NNNC"))
    )
    (comp (ref "C304")
      (value "47nF")
      (footprint "CAP 0201 (0603)")
      (description "Cap Multilayer Ceramic 47nF 6.3V X5R SMT 0201±10% Tolerance")
      (fields
        (field (name "TOLERANCE") "10%")
        (field (name "DIELECTRIC") "X5R")
        (field (name "MANUFACTURER") "Murata")
      )
      (libsource (lib "Western Sydney University - ICNS") (part "Symbol"))
    )
    (comp (ref "C305")
      (value "22nF")
      (footprint "CAP 0201 (0603)")
      (description "Cap Multilayer Ceramic 22nF 10V X5R 0201 ±10% Tolerance")
      (fields
        (field (name "DIELECTRIC") "X5R")
        (field (name "TOLERANCE") "10%")
        (field (name "MANUFACTURER PART NUMBER") "CC0201KRX5R6BB223")
      )
      (libsource (lib "") (part "Symbol_2"))
    )
    (comp (ref "C306")
      (value "10nF")
      (footprint "CAP 0201 (0603)")
      (description "Cap Multilayer Ceramic 10nF 10V X7R 0201 ±10 % Tolerance SMT")
      (fields
        (field (name "VOLTAGE") "10V")
        (field (name "DIELECTRIC") "X7R")
        (field (name "TOLERANCE") "10%")
      )
      (libsource (lib "") (part "Symbol_2"))
    )
    (comp (ref "C307")
      (value "4.7nF")
      (footprint "CAP 0201 (0603)")
      (description "Cap Ceramic 4.7nF 6.3V X7R 10% Pad SMD 0201 125C Automotive T/R")
      (fields
        (field (name "DIELECTRIC") "X7R")
        (field (name "TOLERANCE") "10%")
        (field (name "MANUFACTURER PART NUMBER") "CC0201KRX7R5BB472")
      )
      (libsource (lib "Western Sydney University - ICNS") (part "Symbol"))
    )
    (comp (ref "C308")
      (value "100uF")
      (footprint "CAPCP 0805 (2012)")
      (description "Cap Tant Solid 100uF 6.3V R CASE 20% (2 X 1.35 X 1.35mm) SMD 2012-15 5 Ohm 125°C Plastic T/R")
      (fields
        (field (name "TOLERANCE") "20%")
        (field (name "DIELECTRIC") "Ta")
        (field (name "Comment") "TLCR107M006RTA")
      )
      (libsource (lib "") (part "Symbol_1"))
    )
    (comp (ref "C309")
      (value "1uF")
      (footprint "CAP 0201 (0603)")
      (description "Cap Ceramic 1uF 10V X5R 10% Pad SMD 0201 85C T/R")
      (fields
        (field (name "TOLERANCE") "10%")
        (field (name "DIELECTRIC") "X5R")
        (field (name "MANUFACTURER") "Samsung")
      )
      (libsource (lib "Western Sydney University - ICNS") (part "Symbol"))
    )
    (comp (ref "C310")
      (value "22nF")
      (footprint "CAP 0201 (0603)")
      (description "Cap Multilayer Ceramic 22nF 10V X5R 0201 ±10% Tolerance")
      (fields
        (field (name "DIELECTRIC") "X5R")
        (field (name "TOLERANCE") "10%")
        (field (name "MANUFACTURER PART NUMBER") "CC0201KRX5R6BB223")
      )
      (libsource (lib "") (part "Symbol_2"))
    )
    (comp (ref "C311")
      (value "10nF")
      (footprint "CAP 0201 (0603)")
      (description "Cap Multilayer Ceramic 10nF 10V X7R 0201 ±10 % Tolerance SMT")
      (fields
        (field (name "VOLTAGE") "10V")
        (field (name "DIELECTRIC") "X7R")
        (field (name "TOLERANCE") "10%")
      )
      (libsource (lib "") (part "Symbol_2"))
    )
    (comp (ref "C312")
      (value "0.1uF")
      (footprint "CAP 0201 (0603)")
      (description "Cap Ceramic 0.1uF 10V X5R 10% Pad SMD 0201 85C T/R")
      (fields
        (field (name "MANUFACTURER") "Samsung")
        (field (name "TOLERANCE") "10%")
        (field (name "DIELECTRIC") "X5R")
      )
      (libsource (lib "Western Sydney University - ICNS") (part "CL03A104KP3NNNC"))
    )
    (comp (ref "C313")
      (value "0.1uF")
      (footprint "CAP 0201 (0603)")
      (description "Cap Ceramic 0.1uF 10V X5R 10% Pad SMD 0201 85C T/R")
      (fields
        (field (name "MANUFACTURER") "Samsung")
        (field (name "TOLERANCE") "10%")
        (field (name "DIELECTRIC") "X5R")
      )
      (libsource (lib "Western Sydney University - ICNS") (part "CL03A104KP3NNNC"))
    )
    (comp (ref "C314")
      (value "CC0201KRX7R5BB472")
      (footprint "CAP 0201 (0603)")
      (description "Cap Ceramic 4.7nF 6.3V X7R 10% Pad SMD 0201 125C Automotive T/R")
      (fields
        (field (name "TOLERANCE") "10%")
        (field (name "MANUFACTURER") "Yageo")
        (field (name "CAPACITANCE") "4.7nF")
        (field (name "DIELECTRIC") "X7R")
      )
      (libsource (lib "Western Sydney University - ICNS") (part "Symbol"))
    )
    (comp (ref "C315")
      (value "470nF")
      (footprint "CAP 0201 (0603)")
      (description "Cap Multilayer Ceramic 0.47 uF 10V X5R  0201 10% RoHS  (High dielectric type)")
      (fields
        (field (name "DIELECTRIC") "X5R")
        (field (name "MANUFACTURER") "Taiyo Yuden")
        (field (name "MANUFACTURER PART NUMBER") "LMK063BBJ474KPLF")
      )
      (libsource (lib "Western Sydney University - ICNS") (part "LMK063BBJ474KPLF"))
    )
    (comp (ref "C316")
      (value "0.1uF")
      (footprint "CAP 0201 (0603)")
      (description "Cap Ceramic 0.1uF 10V X5R 10% Pad SMD 0201 85C T/R")
      (fields
        (field (name "MANUFACTURER") "Samsung")
        (field (name "TOLERANCE") "10%")
        (field (name "DIELECTRIC") "X5R")
      )
      (libsource (lib "Western Sydney University - ICNS") (part "CL03A104KP3NNNC"))
    )
    (comp (ref "C317")
      (value "0.1uF")
      (footprint "CAP 0201 (0603)")
      (description "Cap Ceramic 0.1uF 10V X5R 10% Pad SMD 0201 85C T/R")
      (fields
        (field (name "MANUFACTURER") "Samsung")
        (field (name "TOLERANCE") "10%")
        (field (name "DIELECTRIC") "X5R")
      )
      (libsource (lib "Western Sydney University - ICNS") (part "CL03A104KP3NNNC"))
    )
  )
  (nets
    (net (code "1") (name "GND") (class "Default")
      (node (ref "C211") (pin "2") (pinfunction "2_2") (pintype "passive"))
      (node (ref "C212") (pin "2") (pinfunction "2_2") (pintype "passive"))
      (node (ref "C213") (pin "2") (pinfunction "2_2") (pintype "passive"))
      (node (ref "C214") (pin "2") (pinfunction "2_2") (pintype "passive"))
      (node (ref "C215") (pin "2") (pinfunction "2_2") (pintype "passive"))
      (node (ref "C216") (pin "2") (pinfunction "2_2") (pintype "passive"))
      (node (ref "C217") (pin "2") (pinfunction "2_2") (pintype "passive"))
      (node (ref "C218") (pin "2") (pinfunction "2_2") (pintype "passive"))
      (node (ref "C219") (pin "2") (pinfunction "2_2") (pintype "passive"))
      (node (ref "C220") (pin "2") (pinfunction "2_2") (pintype "passive"))
      (node (ref "C221") (pin "2") (pinfunction "2_2") (pintype "passive"))
      (node (ref "C222") (pin "2") (pinfunction "2_2") (pintype "passive"))
      (node (ref "C223") (pin "2") (pinfunction "2_2") (pintype "passive"))
      (node (ref "C224") (pin "2") (pinfunction "2_2") (pintype "passive"))
      (node (ref "C225") (pin "2") (pinfunction "2_2") (pintype "passive"))
      (node (ref "C226") (pin "2") (pinfunction "2_2") (pintype "passive"))
      (node (ref "C227") (pin "2") (pinfunction "2_2") (pintype "passive"))
      (node (ref "C228") (pin "2") (pinfunction "2_2") (pintype "passive"))
      (node (ref "C229") (pin "2") (pinfunction "2_2") (pintype "passive"))
      (node (ref "C230") (pin "2") (pinfunction "2_2") (pintype "passive"))
      (node (ref "C231") (pin "2") (pinfunction "2_2") (pintype "passive"))
      (node (ref "C232") (pin "2") (pinfunction "2_2") (pintype "passive"))
      (node (ref "C233") (pin "2") (pinfunction "2_2") (pintype "passive"))
      (node (ref "C234") (pin "2") (pinfunction "2_2") (pintype "passive"))
      (node (ref "C235") (pin "2") (pinfunction "2_2") (pintype "passive"))
      (node (ref "C236") (pin "2") (pinfunction "2_2") (pintype "passive"))
      (node (ref "C237") (pin "2") (pinfunction "2_2") (pintype "passive"))
      (node (ref "C238") (pin "2") (pinfunction "2_2") (pintype "passive"))
      (node (ref "C239") (pin "2") (pinfunction "2_2") (pintype "passive"))
      (node (ref "C240") (pin "2") (pinfunction "2_2") (pintype "passive"))
      (node (ref "C241") (pin "2") (pinfunction "2_2") (pintype "passive"))
      (node (ref "C242") (pin "2") (pinfunction "2_2") (pintype "passive"))
      (node (ref "C243") (pin "2") (pinfunction "2_2") (pintype "passive"))
      (node (ref "C244") (pin "2") (pinfunction "2_2") (pintype "passive"))
      (node (ref "C245") (pin "2") (pinfunction "2_2") (pintype "passive"))
      (node (ref "C246") (pin "2") (pinfunction "2_2") (pintype "passive"))
      (node (ref "C247") (pin "2") (pinfunction "2_2") (pintype "passive"))
      (node (ref "C248") (pin "2") (pinfunction "2_2") (pintype "passive"))
      (node (ref "C249") (pin "2") (pinfunction "2_2") (pintype "passive"))
      (node (ref "C250") (pin "2") (pinfunction "2_2") (pintype "passive"))
      (node (ref "C251") (pin "2") (pinfunction "2_2") (pintype "passive"))
      (node (ref "C252") (pin "2") (pinfunction "2_2") (pintype "passive"))
      (node (ref "C253") (pin "2") (pinfunction "2_2") (pintype "passive"))
      (node (ref "C254") (pin "2") (pinfunction "2_2") (pintype "passive"))
      (node (ref "C260") (pin "2") (pinfunction "2_2") (pintype "passive"))
      (node (ref "C261") (pin "2") (pinfunction "2_2") (pintype "passive"))
      (node (ref "C262") (pin "2") (pinfunction "2_2") (pintype "passive"))
      (node (ref "C263") (pin "2") (pinfunction "2_2") (pintype "passive"))
      (node (ref "C264") (pin "2") (pinfunction "2_2") (pintype "passive"))
      (node (ref "C265") (pin "2") (pinfunction "2_2") (pintype "passive"))
      (node (ref "C266") (pin "2") (pinfunction "2_2") (pintype "passive"))
      (node (ref "C267") (pin "2") (pinfunction "2_2") (pintype "passive"))
      (node (ref "C268") (pin "2") (pinfunction "2_2") (pintype "passive"))
      (node (ref "C269") (pin "2") (pinfunction "2_2") (pintype "passive"))
      (node (ref "C270") (pin "2") (pinfunction "2_2") (pintype "passive"))
      (node (ref "C271") (pin "2") (pinfunction "2_2") (pintype "passive"))
      (node (ref "C272") (pin "2") (pinfunction "2_2") (pintype "passive"))
      (node (ref "C273") (pin "2") (pinfunction "2_2") (pintype "passive"))
      (node (ref "C274") (pin "2") (pinfunction "2_2") (pintype "passive"))
      (node (ref "C275") (pin "2") (pinfunction "2_2") (pintype "passive"))
      (node (ref "C276") (pin "2") (pinfunction "2_2") (pintype "passive"))
      (node (ref "C277") (pin "2") (pinfunction "2_2") (pintype "passive"))
      (node (ref "C278") (pin "2") (pinfunction "2_2") (pintype "passive"))
      (node (ref "C279") (pin "2") (pinfunction "2_2") (pintype "passive"))
      (node (ref "C280") (pin "2") (pinfunction "2_2") (pintype "passive"))
      (node (ref "C281") (pin "2") (pinfunction "2_2") (pintype "passive"))
      (node (ref "C282") (pin "2") (pinfunction "2_2") (pintype "passive"))
      (node (ref "C283") (pin "2") (pinfunction "2_2") (pintype "passive"))
      (node (ref "C284") (pin "2") (pinfunction "2_2") (pintype "passive"))
      (node (ref "C285") (pin "2") (pinfunction "2_2") (pintype "passive"))
      (node (ref "C286") (pin "2") (pinfunction "2_2") (pintype "passive"))
      (node (ref "C287") (pin "2") (pinfunction "2_2") (pintype "passive"))
      (node (ref "C288") (pin "2") (pinfunction "2_2") (pintype "passive"))
      (node (ref "C289") (pin "2") (pinfunction "2_2") (pintype "passive"))
      (node (ref "C290") (pin "2") (pinfunction "2_2") (pintype "passive"))
      (node (ref "C291") (pin "2") (pinfunction "2_2") (pintype "passive"))
      (node (ref "C292") (pin "2") (pinfunction "2_2") (pintype "passive"))
      (node (ref "C293") (pin "2") (pinfunction "2_2") (pintype "passive"))
      (node (ref "C294") (pin "2") (pinfunction "2_2") (pintype "passive"))
      (node (ref "C295") (pin "2") (pinfunction "2_2") (pintype "passive"))
      (node (ref "C296") (pin "2") (pinfunction "2_2") (pintype "passive"))
      (node (ref "C297") (pin "2") (pinfunction "2_2") (pintype "passive"))
      (node (ref "C298") (pin "2") (pinfunction "2_2") (pintype "passive"))
      (node (ref "C299") (pin "2") (pinfunction "2_2") (pintype "passive"))
      (node (ref "C300") (pin "2") (pinfunction "2_2") (pintype "passive"))
      (node (ref "C301") (pin "2") (pinfunction "2_2") (pintype "passive"))
      (node (ref "C302") (pin "2") (pinfunction "2_2") (pintype "passive"))
      (node (ref "C303") (pin "2") (pinfunction "2_2") (pintype "passive"))
      (node (ref "C304") (pin "2") (pinfunction "2_2") (pintype "passive"))
      (node (ref "C305") (pin "2") (pinfunction "2_2") (pintype "passive"))
      (node (ref "C306") (pin "2") (pinfunction "2_2") (pintype "passive"))
      (node (ref "C307") (pin "2") (pinfunction "2_2") (pintype "passive"))
      (node (ref "C308") (pin "2") (pinfunction "2_2") (pintype "passive"))
      (node (ref "C309") (pin "2") (pinfunction "2_2") (pintype "passive"))
      (node (ref "C310") (pin "2") (pinfunction "2_2") (pintype "passive"))
      (node (ref "C311") (pin "2") (pinfunction "2_2") (pintype "passive"))
      (node (ref "C312") (pin "2") (pinfunction "2_2") (pintype "passive"))
      (node (ref "C313") (pin "2") (pinfunction "2_2") (pintype "passive"))
      (node (ref "C314") (pin "2") (pinfunction "2_2") (pintype "passive"))
      (node (ref "C315") (pin "2") (pinfunction "2_2") (pintype "passive"))
      (node (ref "C316") (pin "2") (pinfunction "2_2") (pintype "passive"))
      (node (ref "C317") (pin "2") (pinfunction "2_2") (pintype "passive"))
    )
    (net (code "2") (name "VCC1P1_HPS") (class "Default")
      (node (ref "C211") (pin "1") (pinfunction "1_1") (pintype "passive"))
      (node (ref "C212") (pin "1") (pinfunction "1_1") (pintype "passive"))
      (node (ref "C213") (pin "1") (pinfunction "1_1") (pintype "passive"))
      (node (ref "C214") (pin "1") (pinfunction "1_1") (pintype "passive"))
      (node (ref "C215") (pin "1") (pinfunction "1_1") (pintype "passive"))
      (node (ref "C216") (pin "1") (pinfunction "1_1") (pintype "passive"))
      (node (ref "C217") (pin "1") (pinfunction "1_1") (pintype "passive"))
      (node (ref "C218") (pin "1") (pinfunction "1_1") (pintype "passive"))
      (node (ref "C219") (pin "1") (pinfunction "1_1") (pintype "passive"))
      (node (ref "C220") (pin "1") (pinfunction "1_1") (pintype "passive"))
      (node (ref "C221") (pin "1") (pinfunction "1_1") (pintype "passive"))
      (node (ref "C222") (pin "1") (pinfunction "1_1") (pintype "passive"))
      (node (ref "C223") (pin "1") (pinfunction "1_1") (pintype "passive"))
      (node (ref "C224") (pin "1") (pinfunction "1_1") (pintype "passive"))
    )
    (net (code "3") (name "VCC1P5_DDR3") (class "Default")
      (node (ref "C236") (pin "1") (pinfunction "1_1") (pintype "passive"))
      (node (ref "C237") (pin "1") (pinfunction "1_1") (pintype "passive"))
      (node (ref "C238") (pin "1") (pinfunction "1_1") (pintype "passive"))
      (node (ref "C239") (pin "1") (pinfunction "1_1") (pintype "passive"))
      (node (ref "C240") (pin "1") (pinfunction "1_1") (pintype "passive"))
      (node (ref "C241") (pin "1") (pinfunction "1_1") (pintype "passive"))
      (node (ref "C242") (pin "1") (pinfunction "1_1") (pintype "passive"))
      (node (ref "C243") (pin "1") (pinfunction "1_1") (pintype "passive"))
      (node (ref "C244") (pin "1") (pinfunction "1_1") (pintype "passive"))
      (node (ref "C245") (pin "1") (pinfunction "1_1") (pintype "passive"))
      (node (ref "C246") (pin "1") (pinfunction "1_1") (pintype "passive"))
      (node (ref "C247") (pin "1") (pinfunction "1_1") (pintype "passive"))
      (node (ref "C248") (pin "1") (pinfunction "1_1") (pintype "passive"))
      (node (ref "C249") (pin "1") (pinfunction "1_1") (pintype "passive"))
      (node (ref "C250") (pin "1") (pinfunction "1_1") (pintype "passive"))
      (node (ref "C251") (pin "1") (pinfunction "1_1") (pintype "passive"))
      (node (ref "C252") (pin "1") (pinfunction "1_1") (pintype "passive"))
    )
    (net (code "4") (name "VCC2P5") (class "Default")
      (node (ref "C253") (pin "1") (pinfunction "1_1") (pintype "passive"))
      (node (ref "C254") (pin "1") (pinfunction "1_1") (pintype "passive"))
      (node (ref "C260") (pin "1") (pinfunction "1_1") (pintype "passive"))
      (node (ref "C261") (pin "1") (pinfunction "1_1") (pintype "passive"))
      (node (ref "C262") (pin "1") (pinfunction "1_1") (pintype "passive"))
      (node (ref "C263") (pin "1") (pinfunction "1_1") (pintype "passive"))
      (node (ref "C264") (pin "1") (pinfunction "1_1") (pintype "passive"))
      (node (ref "C265") (pin "1") (pinfunction "1_1") (pintype "passive"))
      (node (ref "C266") (pin "1") (pinfunction "1_1") (pintype "passive"))
      (node (ref "C267") (pin "1") (pinfunction "1_1") (pintype "passive"))
      (node (ref "C268") (pin "1") (pinfunction "1_1") (pintype "passive"))
      (node (ref "C269") (pin "1") (pinfunction "1_1") (pintype "passive"))
      (node (ref "C270") (pin "1") (pinfunction "1_1") (pintype "passive"))
      (node (ref "C271") (pin "1") (pinfunction "1_1") (pintype "passive"))
      (node (ref "C301") (pin "1") (pinfunction "1_1") (pintype "passive"))
      (node (ref "C302") (pin "1") (pinfunction "1_1") (pintype "passive"))
      (node (ref "C303") (pin "1") (pinfunction "1_1") (pintype "passive"))
      (node (ref "C304") (pin "1") (pinfunction "1_1") (pintype "passive"))
      (node (ref "C305") (pin "1") (pinfunction "1_1") (pintype "passive"))
      (node (ref "C306") (pin "1") (pinfunction "1_1") (pintype "passive"))
      (node (ref "C307") (pin "1") (pinfunction "1_1") (pintype "passive"))
    )
    (net (code "5") (name "VCC3P3") (class "Default")
      (node (ref "C233") (pin "1") (pinfunction "1_1") (pintype "passive"))
      (node (ref "C234") (pin "1") (pinfunction "1_1") (pintype "passive"))
      (node (ref "C235") (pin "1") (pinfunction "1_1") (pintype "passive"))
      (node (ref "C308") (pin "1") (pinfunction "1_1") (pintype "passive"))
      (node (ref "C309") (pin "1") (pinfunction "1_1") (pintype "passive"))
      (node (ref "C310") (pin "1") (pinfunction "1_1") (pintype "passive"))
      (node (ref "C311") (pin "1") (pinfunction "1_1") (pintype "passive"))
      (node (ref "C312") (pin "1") (pinfunction "1_1") (pintype "passive"))
      (node (ref "C313") (pin "1") (pinfunction "1_1") (pintype "passive"))
      (node (ref "C314") (pin "1") (pinfunction "1_1") (pintype "passive"))
      (node (ref "C315") (pin "1") (pinfunction "1_1") (pintype "passive"))
      (node (ref "C316") (pin "1") (pinfunction "1_1") (pintype "passive"))
      (node (ref "C317") (pin "1") (pinfunction "1_1") (pintype "passive"))
    )
    (net (code "6") (name "VCCA_FPLL") (class "Default")
      (node (ref "C228") (pin "1") (pinfunction "1_1") (pintype "passive"))
      (node (ref "C229") (pin "1") (pinfunction "1_1") (pintype "passive"))
    )
    (net (code "7") (name "VCCINT") (class "Default")
      (node (ref "C272") (pin "1") (pinfunction "1_1") (pintype "passive"))
      (node (ref "C273") (pin "1") (pinfunction "1_1") (pintype "passive"))
      (node (ref "C274") (pin "1") (pinfunction "1_1") (pintype "passive"))
      (node (ref "C275") (pin "1") (pinfunction "1_1") (pintype "passive"))
      (node (ref "C276") (pin "1") (pinfunction "1_1") (pintype "passive"))
      (node (ref "C277") (pin "1") (pinfunction "1_1") (pintype "passive"))
      (node (ref "C278") (pin "1") (pinfunction "1_1") (pintype "passive"))
      (node (ref "C279") (pin "1") (pinfunction "1_1") (pintype "passive"))
      (node (ref "C280") (pin "1") (pinfunction "1_1") (pintype "passive"))
      (node (ref "C281") (pin "1") (pinfunction "1_1") (pintype "passive"))
      (node (ref "C282") (pin "1") (pinfunction "1_1") (pintype "passive"))
      (node (ref "C283") (pin "1") (pinfunction "1_1") (pintype "passive"))
      (node (ref "C284") (pin "1") (pinfunction "1_1") (pintype "passive"))
      (node (ref "C285") (pin "1") (pinfunction "1_1") (pintype "passive"))
      (node (ref "C286") (pin "1") (pinfunction "1_1") (pintype "passive"))
      (node (ref "C287") (pin "1") (pinfunction "1_1") (pintype "passive"))
      (node (ref "C288") (pin "1") (pinfunction "1_1") (pintype "passive"))
      (node (ref "C289") (pin "1") (pinfunction "1_1") (pintype "passive"))
      (node (ref "C290") (pin "1") (pinfunction "1_1") (pintype "passive"))
      (node (ref "C291") (pin "1") (pinfunction "1_1") (pintype "passive"))
      (node (ref "C292") (pin "1") (pinfunction "1_1") (pintype "passive"))
      (node (ref "C293") (pin "1") (pinfunction "1_1") (pintype "passive"))
      (node (ref "C294") (pin "1") (pinfunction "1_1") (pintype "passive"))
      (node (ref "C295") (pin "1") (pinfunction "1_1") (pintype "passive"))
      (node (ref "C296") (pin "1") (pinfunction "1_1") (pintype "passive"))
      (node (ref "C297") (pin "1") (pinfunction "1_1") (pintype "passive"))
      (node (ref "C298") (pin "1") (pinfunction "1_1") (pintype "passive"))
      (node (ref "C299") (pin "1") (pinfunction "1_1") (pintype "passive"))
      (node (ref "C300") (pin "1") (pinfunction "1_1") (pintype "passive"))
    )
    (net (code "8") (name "VCC_AUX") (class "Default")
      (node (ref "C225") (pin "1") (pinfunction "1_1") (pintype "passive"))
      (node (ref "C226") (pin "1") (pinfunction "1_1") (pintype "passive"))
      (node (ref "C227") (pin "1") (pinfunction "1_1") (pintype "passive"))
    )
    (net (code "9") (name "VCC_AUX_SHARED") (class "Default")
      (node (ref "C230") (pin "1") (pinfunction "1_1") (pintype "passive"))
      (node (ref "C231") (pin "1") (pinfunction "1_1") (pintype "passive"))
    )
    (net (code "10") (name "VCC_BAT") (class "Default")
      (node (ref "C232") (pin "1") (pinfunction "1_1") (pintype "passive"))
    )
  )
)
